# design.net
KiCad netlist of a schematic drawn in Altium Designer
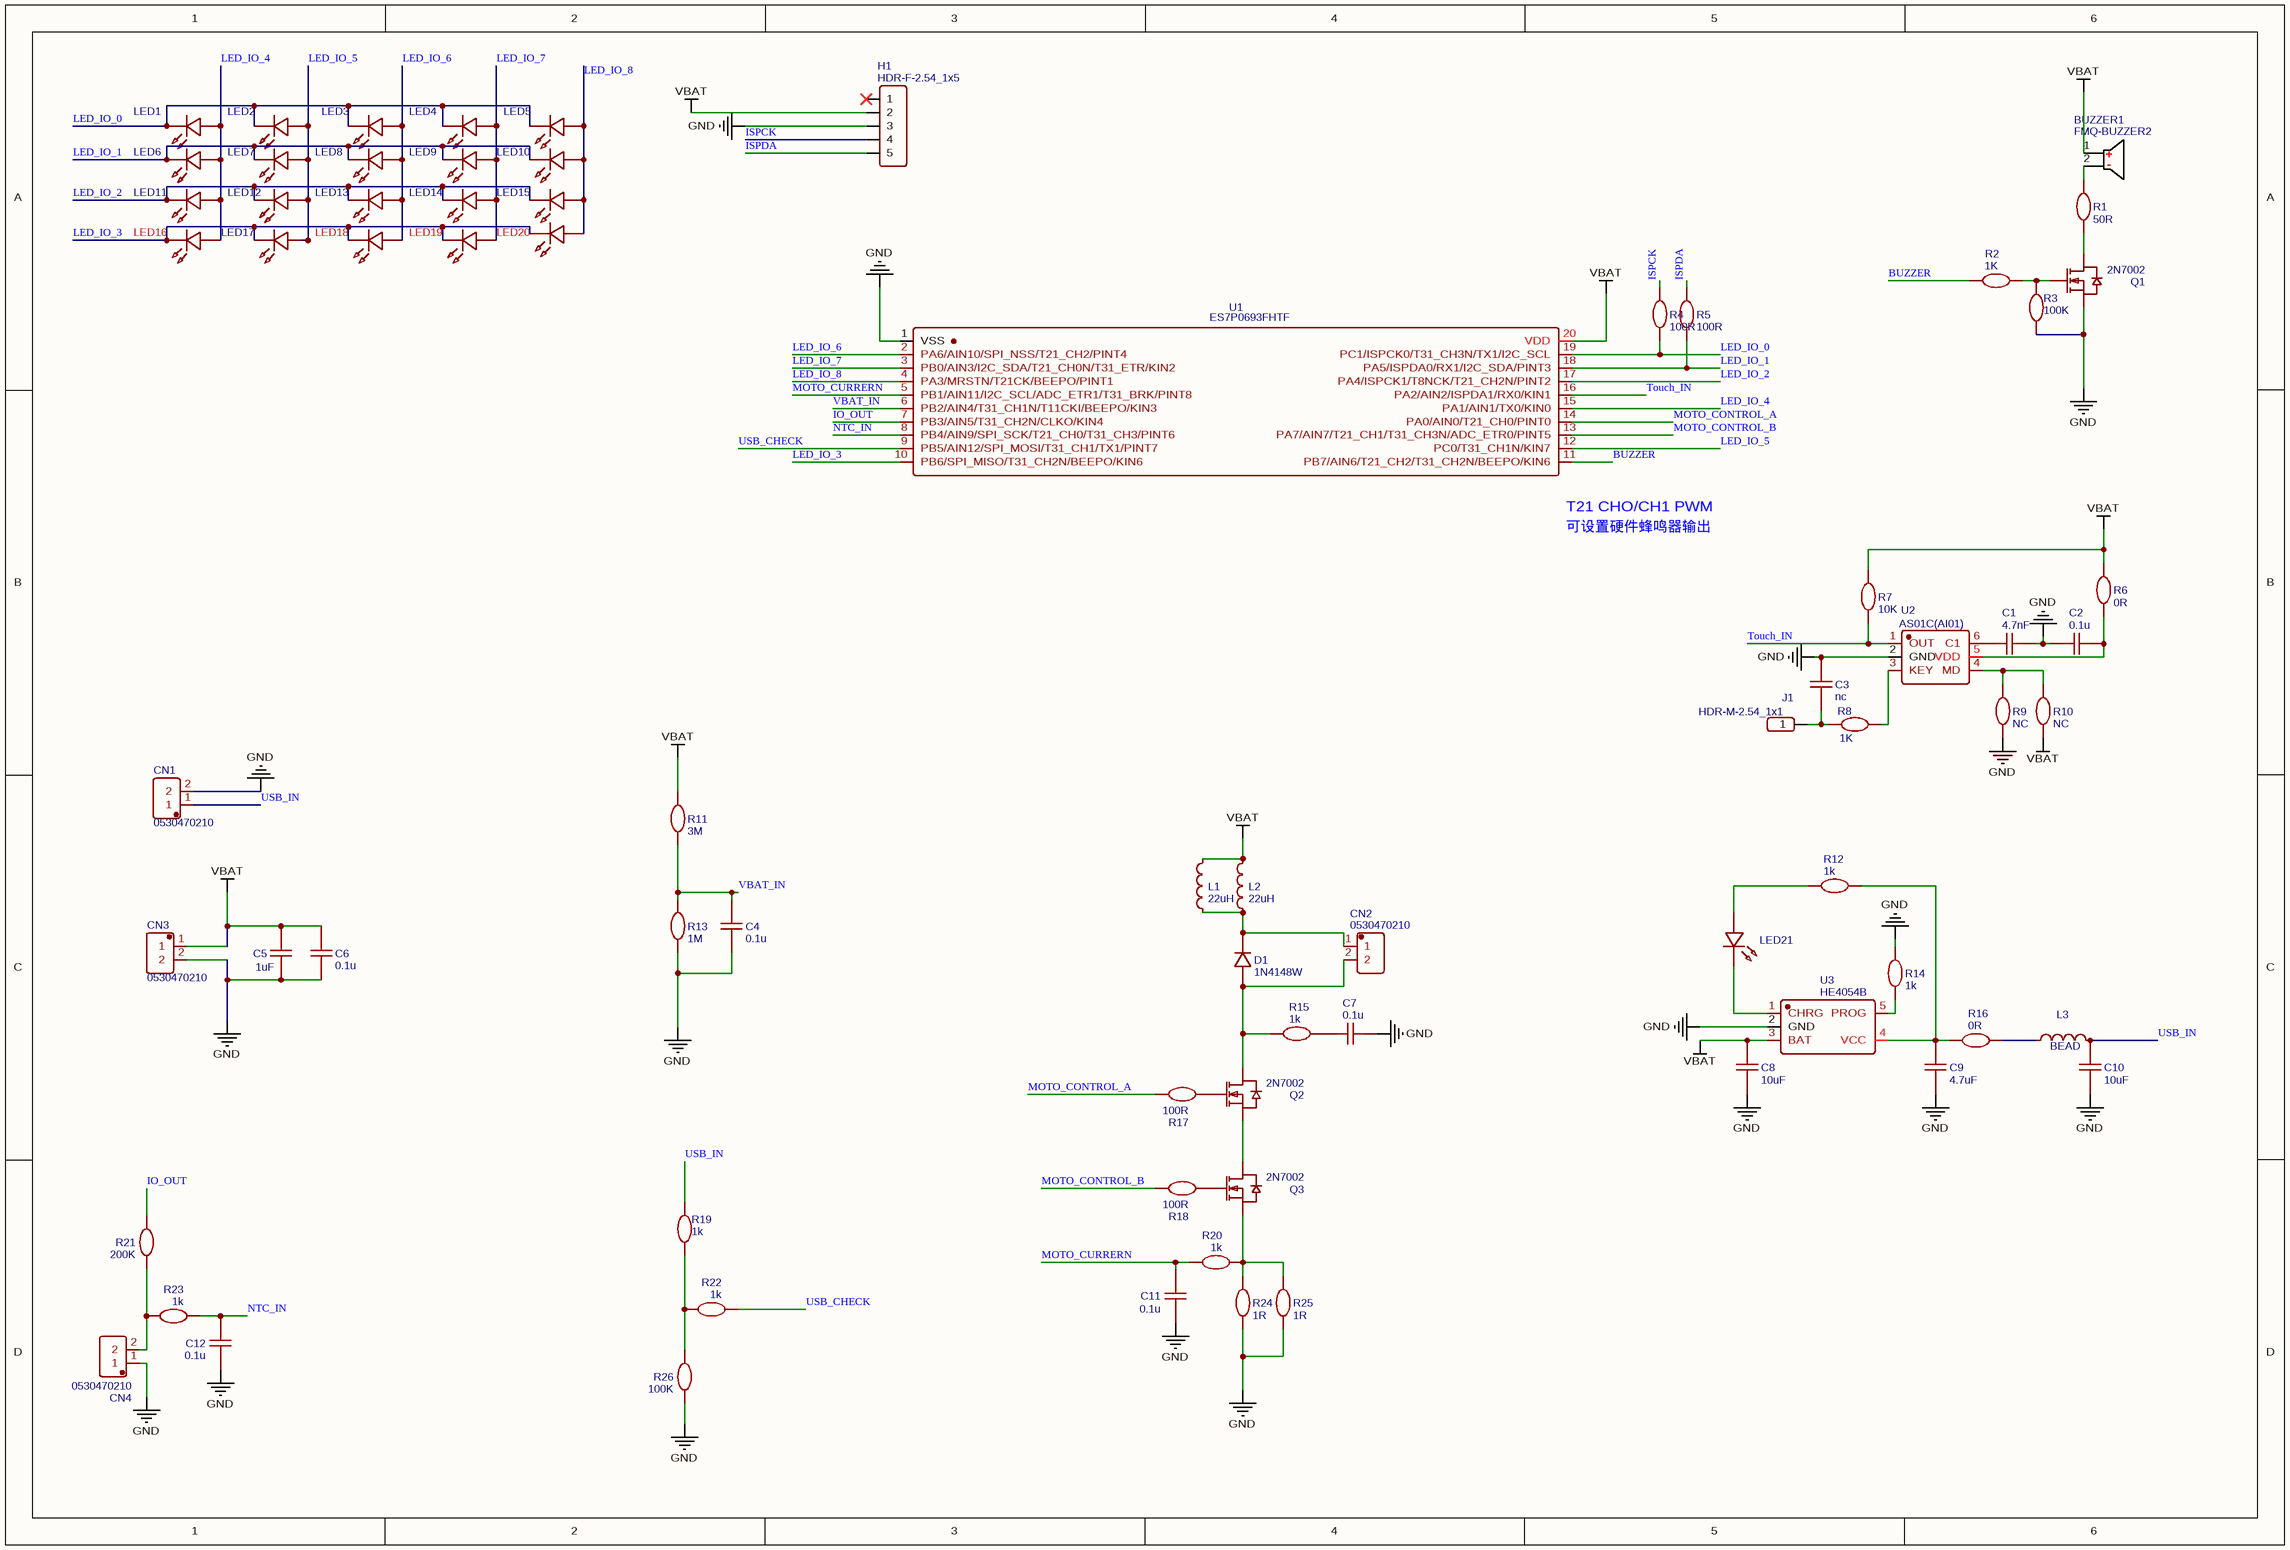
[diagram p0: 搅拌杯原理图.schdoc]

(export (version "E")
  (design (tool "Eeschema 10.0.6"))
  (components
    (comp (ref "BUZZER1")
      (value "FMQ-BUZZER2")
      (footprint "BUZ-TH_BD12.0-P7.60-D0.6-FD")
      (fields (field (name "BOM_SUPPLIER PART") "C9900006103") (field (name "CONTRIBUTOR") "LCSC"))
      (libsource (lib "altium-import") (part "root_0_FMQ-BUZZER2_"))
    )
    (comp (ref "C1")
      (value "4.7nF")
      (footprint "C0603")
      (fields (field (name "CONTRIBUTOR") "LCEDA_Lib"))
      (libsource (lib "altium-import") (part "root_0_4.7nF_"))
    )
    (comp (ref "C2")
      (value "0.1u")
      (footprint "C0603")
      (fields (field (name "CONTRIBUTOR") "LCEDA_Lib"))
      (libsource (lib "altium-import") (part "root_0_0.1u_"))
    )
    (comp (ref "C3")
      (value "nc")
      (footprint "C0603")
      (fields (field (name "CONTRIBUTOR") "LCEDA_Lib"))
      (libsource (lib "altium-import") (part "root_1_nc_"))
    )
    (comp (ref "C4")
      (value "0.1u")
      (footprint "C0603")
      (fields (field (name "CONTRIBUTOR") "LCEDA_Lib"))
      (libsource (lib "") (part "root_1_0.1u__1"))
    )
    (comp (ref "C5")
      (value "1uF")
      (footprint "C0603")
      (fields (field (name "CONTRIBUTOR") "LCEDA_Lib"))
      (libsource (lib "altium-import") (part "root_3_1uF_"))
    )
    (comp (ref "C6")
      (value "0.1u")
      (footprint "C0603")
      (fields (field (name "CONTRIBUTOR") "LCEDA_Lib"))
      (libsource (lib "") (part "root_3_0.1u__1"))
    )
    (comp (ref "C7")
      (value "0.1u")
      (footprint "C0603")
      (fields (field (name "CONTRIBUTOR") "LCEDA_Lib"))
      (libsource (lib "altium-import") (part "root_2_0.1u_"))
    )
    (comp (ref "C8")
      (value "10uF")
      (footprint "C0603")
      (fields (field (name "CONTRIBUTOR") "LCEDA_Lib"))
      (libsource (lib "altium-import") (part "root_1_10uF_"))
    )
    (comp (ref "C9")
      (value "4.7uF")
      (footprint "C0603")
      (fields (field (name "CONTRIBUTOR") "LCEDA_Lib"))
      (libsource (lib "altium-import") (part "root_1_4.7uF_"))
    )
    (comp (ref "C10")
      (value "10uF")
      (footprint "C0603")
      (fields (field (name "CONTRIBUTOR") "LCEDA_Lib"))
      (libsource (lib "altium-import") (part "root_1_10uF_"))
    )
    (comp (ref "C11")
      (value "0.1u")
      (footprint "C0603")
      (fields (field (name "CONTRIBUTOR") "LCEDA_Lib"))
      (libsource (lib "altium-import") (part "root_1_0.1u_"))
    )
    (comp (ref "C12")
      (value "0.1u")
      (footprint "C0603")
      (fields (field (name "CONTRIBUTOR") "LCEDA_Lib"))
      (libsource (lib "altium-import") (part "root_3_0.1u_"))
    )
    (comp (ref "CN1")
      (value "0530470210")
      (footprint "CONN-TH_0530470210")
      (fields (field (name "BOM_SUPPLIER PART") "C114130") (field (name "CONTRIBUTOR") "LCSC"))
      (libsource (lib "") (part "root_0_mirrored_0530470210__1"))
    )
    (comp (ref "CN2")
      (value "0530470210")
      (footprint "CONN-TH_0530470210")
      (fields (field (name "BOM_SUPPLIER PART") "C114130") (field (name "CONTRIBUTOR") "LCSC"))
      (libsource (lib "altium-import") (part "root_0_0530470210_"))
    )
    (comp (ref "CN3")
      (value "0530470210")
      (footprint "CONN-TH_0530470210")
      (fields (field (name "BOM_SUPPLIER PART") "C114130") (field (name "CONTRIBUTOR") "LCSC"))
      (libsource (lib "altium-import") (part "root_0_mirrored_0530470210_"))
    )
    (comp (ref "CN4")
      (value "0530470210")
      (footprint "CONN-TH_0530470210")
      (fields (field (name "BOM_SUPPLIER PART") "C114130") (field (name "CONTRIBUTOR") "LCSC"))
      (libsource (lib "") (part "root_0_0530470210__1"))
    )
    (comp (ref "D1")
      (value "1N4148W")
      (footprint "SOD-123FL_L2.6-W1.6-LS3.4-RD")
      (fields (field (name "BOM_SUPPLIER PART") "C129216") (field (name "CONTRIBUTOR") "LCEDA_Lib"))
      (libsource (lib "altium-import") (part "root_1_1N4148W_"))
    )
    (comp (ref "H1")
      (value "HDR-F-2.54_1x5")
      (footprint "1.27mm_5PIN")
      (fields (field (name "BOM_SUPPLIER PART") "C50950") (field (name "CONTRIBUTOR") "LCEDA_Lib"))
      (libsource (lib "altium-import") (part "root_0_HDR-F-2.54_1x5_"))
    )
    (comp (ref "J1")
      (value "HDR-M-2.54_1x1")
      (footprint "HDR-M-2.54_1X1")
      (fields (field (name "BOM_SUPPLIER PART") "C81276") (field (name "CONTRIBUTOR") "LCEDA_Lib"))
      (libsource (lib "altium-import") (part "root_2_HDR-M-2.54_1x1_"))
    )
    (comp (ref "L1")
      (value "22uH")
      (footprint "L0603")
      (fields (field (name "CONTRIBUTOR") "LCEDA_Lib"))
      (libsource (lib "altium-import") (part "root_1_22uH_"))
    )
    (comp (ref "L2")
      (value "22uH")
      (footprint "L0603")
      (fields (field (name "CONTRIBUTOR") "LCEDA_Lib"))
      (libsource (lib "altium-import") (part "root_1_22uH_"))
    )
    (comp (ref "L3")
      (value "BEAD")
      (footprint "L0603")
      (fields (field (name "CONTRIBUTOR") "LCEDA_Lib"))
      (libsource (lib "altium-import") (part "root_0_22uH_"))
    )
    (comp (ref "LED1")
      (value "LED-0603_W")
      (footprint "LED0603-FD_WHITE")
      (fields
        (field (name "BOM_MANUFACTURER PART") "17-21SURC/S530-A3/TR8")
        (field (name "BOM_SUPPLIER PART") "C72037")
        (field (name "CONTRIBUTOR") "LCEDA_Lib")
      )
      (libsource (lib "altium-import") (part "root_2_LED-0603_W_"))
    )
    (comp (ref "LED2")
      (value "LED-0603_W")
      (footprint "LED0603-FD_WHITE")
      (fields
        (field (name "BOM_MANUFACTURER PART") "17-21SURC/S530-A3/TR8")
        (field (name "BOM_SUPPLIER PART") "C72037")
        (field (name "CONTRIBUTOR") "LCEDA_Lib")
      )
      (libsource (lib "altium-import") (part "root_2_LED-0603_W_"))
    )
    (comp (ref "LED3")
      (value "LED-0603_W")
      (footprint "LED0603-FD_WHITE")
      (fields
        (field (name "BOM_MANUFACTURER PART") "17-21SURC/S530-A3/TR8")
        (field (name "BOM_SUPPLIER PART") "C72037")
        (field (name "CONTRIBUTOR") "LCEDA_Lib")
      )
      (libsource (lib "altium-import") (part "root_2_LED-0603_W_"))
    )
    (comp (ref "LED4")
      (value "LED-0603_W")
      (footprint "LED0603-FD_WHITE")
      (fields
        (field (name "BOM_MANUFACTURER PART") "17-21SURC/S530-A3/TR8")
        (field (name "BOM_SUPPLIER PART") "C72037")
        (field (name "CONTRIBUTOR") "LCEDA_Lib")
      )
      (libsource (lib "altium-import") (part "root_2_LED-0603_W_"))
    )
    (comp (ref "LED5")
      (value "LED-0603_W")
      (footprint "LED0603-FD_WHITE")
      (fields
        (field (name "BOM_MANUFACTURER PART") "17-21SURC/S530-A3/TR8")
        (field (name "BOM_SUPPLIER PART") "C72037")
        (field (name "CONTRIBUTOR") "LCEDA_Lib")
      )
      (libsource (lib "altium-import") (part "root_2_LED-0603_W_"))
    )
    (comp (ref "LED6")
      (value "LED-0603_W")
      (footprint "LED0603-FD_WHITE")
      (fields
        (field (name "BOM_MANUFACTURER PART") "17-21SURC/S530-A3/TR8")
        (field (name "BOM_SUPPLIER PART") "C72037")
        (field (name "CONTRIBUTOR") "LCEDA_Lib")
      )
      (libsource (lib "altium-import") (part "root_2_LED-0603_W_"))
    )
    (comp (ref "LED7")
      (value "LED-0603_W")
      (footprint "LED0603-FD_WHITE")
      (fields
        (field (name "BOM_MANUFACTURER PART") "17-21SURC/S530-A3/TR8")
        (field (name "BOM_SUPPLIER PART") "C72037")
        (field (name "CONTRIBUTOR") "LCEDA_Lib")
      )
      (libsource (lib "altium-import") (part "root_2_LED-0603_W_"))
    )
    (comp (ref "LED8")
      (value "LED-0603_W")
      (footprint "LED0603-FD_WHITE")
      (fields
        (field (name "BOM_MANUFACTURER PART") "17-21SURC/S530-A3/TR8")
        (field (name "BOM_SUPPLIER PART") "C72037")
        (field (name "CONTRIBUTOR") "LCEDA_Lib")
      )
      (libsource (lib "altium-import") (part "root_2_LED-0603_W_"))
    )
    (comp (ref "LED9")
      (value "LED-0603_W")
      (footprint "LED0603-FD_WHITE")
      (fields
        (field (name "BOM_MANUFACTURER PART") "17-21SURC/S530-A3/TR8")
        (field (name "BOM_SUPPLIER PART") "C72037")
        (field (name "CONTRIBUTOR") "LCEDA_Lib")
      )
      (libsource (lib "altium-import") (part "root_2_LED-0603_W_"))
    )
    (comp (ref "LED10")
      (value "LED-0603_W")
      (footprint "LED0603-FD_WHITE")
      (fields
        (field (name "BOM_MANUFACTURER PART") "17-21SURC/S530-A3/TR8")
        (field (name "BOM_SUPPLIER PART") "C72037")
        (field (name "CONTRIBUTOR") "LCEDA_Lib")
      )
      (libsource (lib "altium-import") (part "root_2_LED-0603_W_"))
    )
    (comp (ref "LED11")
      (value "LED-0603_W")
      (footprint "LED0603-FD_WHITE")
      (fields
        (field (name "BOM_MANUFACTURER PART") "17-21SURC/S530-A3/TR8")
        (field (name "BOM_SUPPLIER PART") "C72037")
        (field (name "CONTRIBUTOR") "LCEDA_Lib")
      )
      (libsource (lib "altium-import") (part "root_2_LED-0603_W_"))
    )
    (comp (ref "LED12")
      (value "LED-0603_W")
      (footprint "LED0603-FD_WHITE")
      (fields
        (field (name "BOM_MANUFACTURER PART") "17-21SURC/S530-A3/TR8")
        (field (name "BOM_SUPPLIER PART") "C72037")
        (field (name "CONTRIBUTOR") "LCEDA_Lib")
      )
      (libsource (lib "altium-import") (part "root_2_LED-0603_W_"))
    )
    (comp (ref "LED13")
      (value "LED-0603_W")
      (footprint "LED0603-FD_WHITE")
      (fields
        (field (name "BOM_MANUFACTURER PART") "17-21SURC/S530-A3/TR8")
        (field (name "BOM_SUPPLIER PART") "C72037")
        (field (name "CONTRIBUTOR") "LCEDA_Lib")
      )
      (libsource (lib "altium-import") (part "root_2_LED-0603_W_"))
    )
    (comp (ref "LED14")
      (value "LED-0603_W")
      (footprint "LED0603-FD_WHITE")
      (fields
        (field (name "BOM_MANUFACTURER PART") "17-21SURC/S530-A3/TR8")
        (field (name "BOM_SUPPLIER PART") "C72037")
        (field (name "CONTRIBUTOR") "LCEDA_Lib")
      )
      (libsource (lib "altium-import") (part "root_2_LED-0603_W_"))
    )
    (comp (ref "LED15")
      (value "LED-0603_W")
      (footprint "LED0603-FD_WHITE")
      (fields
        (field (name "BOM_MANUFACTURER PART") "17-21SURC/S530-A3/TR8")
        (field (name "BOM_SUPPLIER PART") "C72037")
        (field (name "CONTRIBUTOR") "LCEDA_Lib")
      )
      (libsource (lib "altium-import") (part "root_2_LED-0603_W_"))
    )
    (comp (ref "LED16")
      (value "LED-0603_W")
      (footprint "LED0603-FD_WHITE")
      (fields
        (field (name "BOM_MANUFACTURER PART") "17-21SURC/S530-A3/TR8")
        (field (name "BOM_SUPPLIER PART") "C72037")
        (field (name "CONTRIBUTOR") "LCEDA_Lib")
      )
      (libsource (lib "altium-import") (part "root_2_LED-0603_W_"))
    )
    (comp (ref "LED17")
      (value "LED-0603_W")
      (footprint "LED0603-FD_WHITE")
      (fields
        (field (name "BOM_MANUFACTURER PART") "17-21SURC/S530-A3/TR8")
        (field (name "BOM_SUPPLIER PART") "C72037")
        (field (name "CONTRIBUTOR") "LCEDA_Lib")
      )
      (libsource (lib "altium-import") (part "root_2_LED-0603_W_"))
    )
    (comp (ref "LED18")
      (value "LED-0603_W")
      (footprint "LED0603-FD_WHITE")
      (fields
        (field (name "BOM_MANUFACTURER PART") "17-21SURC/S530-A3/TR8")
        (field (name "BOM_SUPPLIER PART") "C72037")
        (field (name "CONTRIBUTOR") "LCEDA_Lib")
      )
      (libsource (lib "altium-import") (part "root_2_LED-0603_W_"))
    )
    (comp (ref "LED19")
      (value "LED-0603_W")
      (footprint "LED0603-FD_WHITE")
      (fields
        (field (name "BOM_MANUFACTURER PART") "17-21SURC/S530-A3/TR8")
        (field (name "BOM_SUPPLIER PART") "C72037")
        (field (name "CONTRIBUTOR") "LCEDA_Lib")
      )
      (libsource (lib "altium-import") (part "root_2_LED-0603_W_"))
    )
    (comp (ref "LED20")
      (value "LED-0603_W")
      (footprint "LED0603-FD_WHITE")
      (fields
        (field (name "BOM_MANUFACTURER PART") "17-21SURC/S530-A3/TR8")
        (field (name "BOM_SUPPLIER PART") "C72037")
        (field (name "CONTRIBUTOR") "LCEDA_Lib")
      )
      (libsource (lib "altium-import") (part "root_2_LED-0603_W_"))
    )
    (comp (ref "LED21")
      (value "LED-0603_W")
      (footprint "LED0603-FD_WHITE")
      (fields
        (field (name "BOM_MANUFACTURER PART") "17-21SURC/S530-A3/TR8")
        (field (name "BOM_SUPPLIER PART") "C72037")
        (field (name "CONTRIBUTOR") "LCEDA_Lib")
      )
      (libsource (lib "altium-import") (part "root_3_LED-0603_W_"))
    )
    (comp (ref "Q1")
      (value "2N7002")
      (footprint "SOT-23_L2.9-W1.3-P0.95-LS2.4-BR")
      (fields
        (field (name "BOM_MANUFACTURER PART") "2N7002,215")
        (field (name "BOM_SUPPLIER PART") "C65189")
        (field (name "CONTRIBUTOR") "LCEDA_Lib")
      )
      (libsource (lib "altium-import") (part "root_2_2N7002_"))
    )
    (comp (ref "Q2")
      (value "2N7002")
      (footprint "SOT-23_L2.9-W1.3-P0.95-LS2.4-BR")
      (fields
        (field (name "BOM_MANUFACTURER PART") "2N7002,215")
        (field (name "BOM_SUPPLIER PART") "C65189")
        (field (name "CONTRIBUTOR") "LCEDA_Lib")
      )
      (libsource (lib "altium-import") (part "root_2_2N7002_"))
    )
    (comp (ref "Q3")
      (value "2N7002")
      (footprint "SOT-23_L2.9-W1.3-P0.95-LS2.4-BR")
      (fields
        (field (name "BOM_MANUFACTURER PART") "2N7002,215")
        (field (name "BOM_SUPPLIER PART") "C65189")
        (field (name "CONTRIBUTOR") "LCEDA_Lib")
      )
      (libsource (lib "altium-import") (part "root_2_2N7002_"))
    )
    (comp (ref "R1")
      (value "50R")
      (footprint "R0603")
      (fields (field (name "CONTRIBUTOR") "LCEDA_Lib"))
      (libsource (lib "altium-import") (part "root_3_100R_"))
    )
    (comp (ref "R2")
      (value "1K")
      (footprint "R0603")
      (fields (field (name "CONTRIBUTOR") "LCEDA_Lib"))
      (libsource (lib "altium-import") (part "root_2_1K_"))
    )
    (comp (ref "R3")
      (value "100K")
      (footprint "R0603")
      (fields (field (name "CONTRIBUTOR") "LCEDA_Lib"))
      (libsource (lib "altium-import") (part "root_3_1K_"))
    )
    (comp (ref "R4")
      (value "100R")
      (footprint "R0603")
      (fields (field (name "CONTRIBUTOR") "LCEDA_Lib"))
      (libsource (lib "altium-import") (part "root_3_100R_"))
    )
    (comp (ref "R5")
      (value "100R")
      (footprint "R0603")
      (fields (field (name "CONTRIBUTOR") "LCEDA_Lib"))
      (libsource (lib "altium-import") (part "root_3_100R_"))
    )
    (comp (ref "R6")
      (value "0R")
      (footprint "R0603")
      (fields (field (name "CONTRIBUTOR") "LCEDA_Lib"))
      (libsource (lib "altium-import") (part "root_1_NC_"))
    )
    (comp (ref "R7")
      (value "10K")
      (footprint "R0603")
      (fields (field (name "CONTRIBUTOR") "LCEDA_Lib"))
      (libsource (lib "altium-import") (part "root_1_NC_"))
    )
    (comp (ref "R8")
      (value "1K")
      (footprint "R0603")
      (fields (field (name "CONTRIBUTOR") "LCEDA_Lib"))
      (libsource (lib "altium-import") (part "root_2_1K_"))
    )
    (comp (ref "R9")
      (value "NC")
      (footprint "R0603")
      (fields (field (name "CONTRIBUTOR") "LCEDA_Lib"))
      (libsource (lib "altium-import") (part "root_1_NC_"))
    )
    (comp (ref "R10")
      (value "NC")
      (footprint "R0603")
      (fields (field (name "CONTRIBUTOR") "LCEDA_Lib"))
      (libsource (lib "altium-import") (part "root_1_NC_"))
    )
    (comp (ref "R11")
      (value "3M")
      (footprint "R0603")
      (fields (field (name "CONTRIBUTOR") "LCEDA_Lib"))
      (libsource (lib "altium-import") (part "root_1_430k_"))
    )
    (comp (ref "R12")
      (value "1k")
      (footprint "R0603")
      (fields (field (name "CONTRIBUTOR") "LCEDA_Lib"))
      (libsource (lib "") (part "root_2_1k__1"))
    )
    (comp (ref "R13")
      (value "1M")
      (footprint "R0603")
      (fields (field (name "CONTRIBUTOR") "LCEDA_Lib"))
      (libsource (lib "altium-import") (part "root_1_430K_"))
    )
    (comp (ref "R14")
      (value "1k")
      (footprint "R0603")
      (fields (field (name "CONTRIBUTOR") "LCEDA_Lib"))
      (libsource (lib "altium-import") (part "root_1_1k_"))
    )
    (comp (ref "R15")
      (value "1k")
      (footprint "R0603")
      (fields (field (name "CONTRIBUTOR") "LCEDA_Lib"))
      (libsource (lib "") (part "root_2_1k__1"))
    )
    (comp (ref "R16")
      (value "0R")
      (footprint "R0603")
      (fields (field (name "CONTRIBUTOR") "LCEDA_Lib"))
      (libsource (lib "altium-import") (part "root_0_NC_"))
    )
    (comp (ref "R17")
      (value "100R")
      (footprint "R0603")
      (fields (field (name "CONTRIBUTOR") "LCEDA_Lib"))
      (libsource (lib "altium-import") (part "root_2_100R_"))
    )
    (comp (ref "R18")
      (value "100R")
      (footprint "R0603")
      (fields (field (name "CONTRIBUTOR") "LCEDA_Lib"))
      (libsource (lib "altium-import") (part "root_2_100R_"))
    )
    (comp (ref "R19")
      (value "1k")
      (footprint "R0603")
      (fields (field (name "CONTRIBUTOR") "LCEDA_Lib"))
      (libsource (lib "altium-import") (part "root_3_1k_"))
    )
    (comp (ref "R20")
      (value "1k")
      (footprint "R0603")
      (fields (field (name "CONTRIBUTOR") "LCEDA_Lib"))
      (libsource (lib "altium-import") (part "root_0_1k_"))
    )
    (comp (ref "R21")
      (value "200K")
      (footprint "R0603")
      (fields (field (name "CONTRIBUTOR") "LCEDA_Lib"))
      (libsource (lib "altium-import") (part "root_3_33K_"))
    )
    (comp (ref "R22")
      (value "1k")
      (footprint "R0603")
      (fields (field (name "CONTRIBUTOR") "LCEDA_Lib"))
      (libsource (lib "altium-import") (part "root_2_1k_"))
    )
    (comp (ref "R23")
      (value "1k")
      (footprint "R0603")
      (fields (field (name "CONTRIBUTOR") "LCEDA_Lib"))
      (libsource (lib "altium-import") (part "root_2_1k_"))
    )
    (comp (ref "R24")
      (value "1R")
      (footprint "R1206")
      (fields (field (name "CONTRIBUTOR") "LCEDA_Lib"))
      (libsource (lib "altium-import") (part "root_1_1R_"))
    )
    (comp (ref "R25")
      (value "1R")
      (footprint "R1206")
      (fields (field (name "CONTRIBUTOR") "LCEDA_Lib"))
      (libsource (lib "altium-import") (part "root_1_1R_"))
    )
    (comp (ref "R26")
      (value "100K")
      (footprint "R0603")
      (fields (field (name "CONTRIBUTOR") "LCEDA_Lib"))
      (libsource (lib "altium-import") (part "root_3_33K_"))
    )
    (comp (ref "U1")
      (value "ES7P0693FHTF")
      (footprint "TSOP20")
      (fields (field (name "CONTRIBUTOR") "zime_zl"))
      (libsource (lib "altium-import") (part "root_0_ES7P0693FHTF_"))
    )
    (comp (ref "U2")
      (value "AS01C(AI01)")
      (footprint "SOT-23-6_L2.9-W1.6-P0.95-LS2.8-BL")
      (fields (field (name "BOM_SUPPLIER PART") "C389617") (field (name "CONTRIBUTOR") "LCSC"))
      (libsource (lib "altium-import") (part "root_0_AS01C(AI01)_"))
    )
    (comp (ref "U3")
      (value "HE4054B")
      (footprint "SOT-23-5_L3.0-W1.7-P0.95-LS2.8-BR")
      (fields (field (name "BOM_SUPPLIER PART") "C711953") (field (name "CONTRIBUTOR") "LCSC"))
      (libsource (lib "altium-import") (part "root_0_HE4054B_"))
    )
  )
  (nets
    (net (code "1") (name "/BUZZER") (class "Default")
      (node (ref "R2") (pin "2") (pinfunction "2_2") (pintype "passive"))
      (node (ref "U1") (pin "11") (pinfunction "PB7/AIN6/T21_CH2/T31_CH2N/BEEPO/KIN6_11") (pintype "passive"))
    )
    (net (code "2") (name "/IO_OUT") (class "Default")
      (node (ref "R21") (pin "1") (pinfunction "1_1") (pintype "passive"))
      (node (ref "U1") (pin "7") (pinfunction "PB3/AIN5/T31_CH2N/CLKO/KIN4_7") (pintype "passive"))
    )
    (net (code "3") (name "/ISPCK") (class "Default")
      (node (ref "H1") (pin "4") (pinfunction "4_4") (pintype "passive"))
      (node (ref "R4") (pin "1") (pinfunction "1_1") (pintype "passive"))
    )
    (net (code "4") (name "/ISPDA") (class "Default")
      (node (ref "H1") (pin "5") (pinfunction "5_5") (pintype "passive"))
      (node (ref "R5") (pin "1") (pinfunction "1_1") (pintype "passive"))
    )
    (net (code "5") (name "/LED_IO_0") (class "Default")
      (node (ref "LED1") (pin "2") (pinfunction "2_2") (pintype "passive"))
      (node (ref "LED2") (pin "2") (pinfunction "2_2") (pintype "passive"))
      (node (ref "LED3") (pin "2") (pinfunction "2_2") (pintype "passive"))
      (node (ref "LED4") (pin "2") (pinfunction "2_2") (pintype "passive"))
      (node (ref "LED5") (pin "2") (pinfunction "2_2") (pintype "passive"))
      (node (ref "R4") (pin "2") (pinfunction "2_2") (pintype "passive"))
      (node (ref "U1") (pin "19") (pinfunction "PC1/ISPCK0/T31_CH3N/TX1/I2C_SCL_19") (pintype "passive"))
    )
    (net (code "6") (name "/LED_IO_1") (class "Default")
      (node (ref "LED10") (pin "2") (pinfunction "2_2") (pintype "passive"))
      (node (ref "LED6") (pin "2") (pinfunction "2_2") (pintype "passive"))
      (node (ref "LED7") (pin "2") (pinfunction "2_2") (pintype "passive"))
      (node (ref "LED8") (pin "2") (pinfunction "2_2") (pintype "passive"))
      (node (ref "LED9") (pin "2") (pinfunction "2_2") (pintype "passive"))
      (node (ref "R5") (pin "2") (pinfunction "2_2") (pintype "passive"))
      (node (ref "U1") (pin "18") (pinfunction "PA5/ISPDA0/RX1/I2C_SDA/PINT3_18") (pintype "passive"))
    )
    (net (code "7") (name "/LED_IO_2") (class "Default")
      (node (ref "LED11") (pin "2") (pinfunction "2_2") (pintype "passive"))
      (node (ref "LED12") (pin "2") (pinfunction "2_2") (pintype "passive"))
      (node (ref "LED13") (pin "2") (pinfunction "2_2") (pintype "passive"))
      (node (ref "LED14") (pin "2") (pinfunction "2_2") (pintype "passive"))
      (node (ref "LED15") (pin "2") (pinfunction "2_2") (pintype "passive"))
      (node (ref "U1") (pin "17") (pinfunction "PA4/ISPCK1/T8NCK/T21_CH2N/PINT2_17") (pintype "passive"))
    )
    (net (code "8") (name "/LED_IO_3") (class "Default")
      (node (ref "LED16") (pin "2") (pinfunction "2_2") (pintype "passive"))
      (node (ref "LED17") (pin "2") (pinfunction "2_2") (pintype "passive"))
      (node (ref "LED18") (pin "2") (pinfunction "2_2") (pintype "passive"))
      (node (ref "LED19") (pin "2") (pinfunction "2_2") (pintype "passive"))
      (node (ref "LED20") (pin "2") (pinfunction "2_2") (pintype "passive"))
      (node (ref "U1") (pin "10") (pinfunction "PB6/SPI_MISO/T31_CH2N/BEEPO/KIN6_10") (pintype "passive"))
    )
    (net (code "9") (name "/LED_IO_4") (class "Default")
      (node (ref "LED1") (pin "1") (pinfunction "1_1") (pintype "passive"))
      (node (ref "LED11") (pin "1") (pinfunction "1_1") (pintype "passive"))
      (node (ref "LED16") (pin "1") (pinfunction "1_1") (pintype "passive"))
      (node (ref "LED6") (pin "1") (pinfunction "1_1") (pintype "passive"))
      (node (ref "U1") (pin "15") (pinfunction "PA1/AIN1/TX0/KIN0_15") (pintype "passive"))
    )
    (net (code "10") (name "/LED_IO_5") (class "Default")
      (node (ref "LED12") (pin "1") (pinfunction "1_1") (pintype "passive"))
      (node (ref "LED17") (pin "1") (pinfunction "1_1") (pintype "passive"))
      (node (ref "LED2") (pin "1") (pinfunction "1_1") (pintype "passive"))
      (node (ref "LED7") (pin "1") (pinfunction "1_1") (pintype "passive"))
      (node (ref "U1") (pin "12") (pinfunction "PC0/T31_CH1N/KIN7_12") (pintype "passive"))
    )
    (net (code "11") (name "/LED_IO_6") (class "Default")
      (node (ref "LED13") (pin "1") (pinfunction "1_1") (pintype "passive"))
      (node (ref "LED18") (pin "1") (pinfunction "1_1") (pintype "passive"))
      (node (ref "LED3") (pin "1") (pinfunction "1_1") (pintype "passive"))
      (node (ref "LED8") (pin "1") (pinfunction "1_1") (pintype "passive"))
      (node (ref "U1") (pin "2") (pinfunction "PA6/AIN10/SPI_NSS/T21_CH2/PINT4_2") (pintype "passive"))
    )
    (net (code "12") (name "/LED_IO_7") (class "Default")
      (node (ref "LED14") (pin "1") (pinfunction "1_1") (pintype "passive"))
      (node (ref "LED19") (pin "1") (pinfunction "1_1") (pintype "passive"))
      (node (ref "LED4") (pin "1") (pinfunction "1_1") (pintype "passive"))
      (node (ref "LED9") (pin "1") (pinfunction "1_1") (pintype "passive"))
      (node (ref "U1") (pin "3") (pinfunction "PB0/AIN3/I2C_SDA/T21_CH0N/T31_ETR/KIN2_3") (pintype "passive"))
    )
    (net (code "13") (name "/LED_IO_8") (class "Default")
      (node (ref "LED10") (pin "1") (pinfunction "1_1") (pintype "passive"))
      (node (ref "LED15") (pin "1") (pinfunction "1_1") (pintype "passive"))
      (node (ref "LED20") (pin "1") (pinfunction "1_1") (pintype "passive"))
      (node (ref "LED5") (pin "1") (pinfunction "1_1") (pintype "passive"))
      (node (ref "U1") (pin "4") (pinfunction "PA3/MRSTN/T21CK/BEEPO/PINT1_4") (pintype "passive"))
    )
    (net (code "14") (name "/MOTO_CONTROL_A") (class "Default")
      (node (ref "R17") (pin "1") (pinfunction "1_1") (pintype "passive"))
      (node (ref "U1") (pin "14") (pinfunction "PA0/AIN0/T21_CH0/PINT0_14") (pintype "passive"))
    )
    (net (code "15") (name "/MOTO_CONTROL_B") (class "Default")
      (node (ref "R18") (pin "1") (pinfunction "1_1") (pintype "passive"))
      (node (ref "U1") (pin "13") (pinfunction "PA7/AIN7/T21_CH1/T31_CH3N/ADC_ETR0/PINT5_13") (pintype "passive"))
    )
    (net (code "16") (name "/MOTO_CURRERN") (class "Default")
      (node (ref "C11") (pin "2") (pinfunction "2_2") (pintype "passive"))
      (node (ref "R20") (pin "2") (pinfunction "2_2") (pintype "passive"))
      (node (ref "U1") (pin "5") (pinfunction "PB1/AIN11/I2C_SCL/ADC_ETR1/T31_BRK/PINT8_5") (pintype "passive"))
    )
    (net (code "17") (name "/NTC_IN") (class "Default")
      (node (ref "C12") (pin "1") (pinfunction "1_1") (pintype "passive"))
      (node (ref "R23") (pin "2") (pinfunction "2_2") (pintype "passive"))
      (node (ref "U1") (pin "8") (pinfunction "PB4/AIN9/SPI_SCK/T21_CH0/T31_CH3/PINT6_8") (pintype "passive"))
    )
    (net (code "18") (name "/Touch_IN") (class "Default")
      (node (ref "R7") (pin "1") (pinfunction "1_1") (pintype "passive"))
      (node (ref "U1") (pin "16") (pinfunction "PA2/AIN2/ISPDA1/RX0/KIN1_16") (pintype "passive"))
      (node (ref "U2") (pin "1") (pinfunction "OUT_1") (pintype "passive"))
    )
    (net (code "19") (name "/USB_CHECK") (class "Default")
      (node (ref "R22") (pin "2") (pinfunction "2_2") (pintype "passive"))
      (node (ref "U1") (pin "9") (pinfunction "PB5/AIN12/SPI_MOSI/T31_CH1/TX1/PINT7_9") (pintype "passive"))
    )
    (net (code "20") (name "/USB_IN") (class "Default")
      (node (ref "C10") (pin "2") (pinfunction "2_2") (pintype "passive"))
      (node (ref "CN1") (pin "1") (pinfunction "1_1") (pintype "passive"))
      (node (ref "L3") (pin "2") (pinfunction "2_2") (pintype "passive"))
      (node (ref "R19") (pin "2") (pinfunction "2_2") (pintype "passive"))
    )
    (net (code "21") (name "/VBAT_IN") (class "Default")
      (node (ref "C4") (pin "2") (pinfunction "2_2") (pintype "passive"))
      (node (ref "R11") (pin "1") (pinfunction "1_1") (pintype "passive"))
      (node (ref "R13") (pin "2") (pinfunction "2_2") (pintype "passive"))
      (node (ref "U1") (pin "6") (pinfunction "PB2/AIN4/T31_CH1N/T11CKI/BEEPO/KIN3_6") (pintype "passive"))
    )
    (net (code "22") (name "GND") (class "Default")
      (node (ref "C1") (pin "2") (pinfunction "2_2") (pintype "passive"))
      (node (ref "C10") (pin "1") (pinfunction "1_1") (pintype "passive"))
      (node (ref "C11") (pin "1") (pinfunction "1_1") (pintype "passive"))
      (node (ref "C12") (pin "2") (pinfunction "2_2") (pintype "passive"))
      (node (ref "C2") (pin "1") (pinfunction "1_1") (pintype "passive"))
      (node (ref "C3") (pin "2") (pinfunction "2_2") (pintype "passive"))
      (node (ref "C4") (pin "1") (pinfunction "1_1") (pintype "passive"))
      (node (ref "C5") (pin "2") (pinfunction "2_2") (pintype "passive"))
      (node (ref "C6") (pin "2") (pinfunction "2_2") (pintype "passive"))
      (node (ref "C7") (pin "1") (pinfunction "1_1") (pintype "passive"))
      (node (ref "C8") (pin "1") (pinfunction "1_1") (pintype "passive"))
      (node (ref "C9") (pin "1") (pinfunction "1_1") (pintype "passive"))
      (node (ref "CN1") (pin "2") (pinfunction "2_2") (pintype "passive"))
      (node (ref "CN3") (pin "2") (pinfunction "2_2") (pintype "passive"))
      (node (ref "CN4") (pin "1") (pinfunction "1_1") (pintype "passive"))
      (node (ref "H1") (pin "3") (pinfunction "3_3") (pintype "passive"))
      (node (ref "Q1") (pin "2") (pinfunction "S_2") (pintype "passive"))
      (node (ref "R13") (pin "1") (pinfunction "1_1") (pintype "passive"))
      (node (ref "R14") (pin "2") (pinfunction "2_2") (pintype "passive"))
      (node (ref "R24") (pin "1") (pinfunction "1_1") (pintype "passive"))
      (node (ref "R25") (pin "1") (pinfunction "1_1") (pintype "passive"))
      (node (ref "R26") (pin "2") (pinfunction "2_2") (pintype "passive"))
      (node (ref "R3") (pin "2") (pinfunction "2_2") (pintype "passive"))
      (node (ref "R9") (pin "1") (pinfunction "1_1") (pintype "passive"))
      (node (ref "U1") (pin "1") (pinfunction "VSS_1") (pintype "passive"))
      (node (ref "U2") (pin "2") (pinfunction "GND_2") (pintype "passive"))
      (node (ref "U3") (pin "2") (pinfunction "GND_2") (pintype "passive"))
    )
    (net (code "23") (name "Net-(BUZZER1-Pad2)") (class "Default")
      (node (ref "BUZZER1") (pin "2") (pinfunction "2_2") (pintype "passive"))
      (node (ref "R1") (pin "1") (pinfunction "1_1") (pintype "passive"))
    )
    (net (code "24") (name "Net-(C3-Pad1)") (class "Default")
      (node (ref "C3") (pin "1") (pinfunction "1_1") (pintype "passive"))
      (node (ref "J1") (pin "1") (pinfunction "1_1") (pintype "passive"))
      (node (ref "R8") (pin "2") (pinfunction "2_2") (pintype "passive"))
    )
    (net (code "25") (name "Net-(C7-Pad2)") (class "Default")
      (node (ref "C7") (pin "2") (pinfunction "2_2") (pintype "passive"))
      (node (ref "R15") (pin "1") (pinfunction "1_1") (pintype "passive"))
    )
    (net (code "26") (name "Net-(CN2-Pad1)") (class "Default")
      (node (ref "CN2") (pin "1") (pinfunction "1_1") (pintype "passive"))
      (node (ref "D1") (pin "1") (pinfunction "1_1") (pintype "passive"))
      (node (ref "L1") (pin "1") (pinfunction "1_1") (pintype "passive"))
      (node (ref "L2") (pin "1") (pinfunction "1_1") (pintype "passive"))
    )
    (net (code "27") (name "Net-(CN4-Pad2)") (class "Default")
      (node (ref "CN4") (pin "2") (pinfunction "2_2") (pintype "passive"))
      (node (ref "R21") (pin "2") (pinfunction "2_2") (pintype "passive"))
      (node (ref "R23") (pin "1") (pinfunction "1_1") (pintype "passive"))
    )
    (net (code "28") (name "Net-(L3-Pad1)") (class "Default")
      (node (ref "L3") (pin "1") (pinfunction "1_1") (pintype "passive"))
      (node (ref "R16") (pin "2") (pinfunction "2_2") (pintype "passive"))
    )
    (net (code "29") (name "Net-(LED21-Pad1)") (class "Default")
      (node (ref "LED21") (pin "1") (pinfunction "1_1") (pintype "passive"))
      (node (ref "R12") (pin "2") (pinfunction "2_2") (pintype "passive"))
    )
    (net (code "30") (name "Net-(Q1-D)") (class "Default")
      (node (ref "Q1") (pin "3") (pinfunction "D_3") (pintype "passive"))
      (node (ref "R1") (pin "2") (pinfunction "2_2") (pintype "passive"))
    )
    (net (code "31") (name "Net-(Q1-G)") (class "Default")
      (node (ref "Q1") (pin "1") (pinfunction "G_1") (pintype "passive"))
      (node (ref "R2") (pin "1") (pinfunction "1_1") (pintype "passive"))
      (node (ref "R3") (pin "1") (pinfunction "1_1") (pintype "passive"))
    )
    (net (code "32") (name "Net-(Q2-D)") (class "Default")
      (node (ref "CN2") (pin "2") (pinfunction "2_2") (pintype "passive"))
      (node (ref "D1") (pin "2") (pinfunction "2_2") (pintype "passive"))
      (node (ref "Q2") (pin "3") (pinfunction "D_3") (pintype "passive"))
      (node (ref "R15") (pin "2") (pinfunction "2_2") (pintype "passive"))
    )
    (net (code "33") (name "Net-(Q2-G)") (class "Default")
      (node (ref "Q2") (pin "1") (pinfunction "G_1") (pintype "passive"))
      (node (ref "R17") (pin "2") (pinfunction "2_2") (pintype "passive"))
    )
    (net (code "34") (name "Net-(Q2-S)") (class "Default")
      (node (ref "Q2") (pin "2") (pinfunction "S_2") (pintype "passive"))
      (node (ref "Q3") (pin "3") (pinfunction "D_3") (pintype "passive"))
    )
    (net (code "35") (name "Net-(Q3-G)") (class "Default")
      (node (ref "Q3") (pin "1") (pinfunction "G_1") (pintype "passive"))
      (node (ref "R18") (pin "2") (pinfunction "2_2") (pintype "passive"))
    )
    (net (code "36") (name "Net-(Q3-S)") (class "Default")
      (node (ref "Q3") (pin "2") (pinfunction "S_2") (pintype "passive"))
      (node (ref "R20") (pin "1") (pinfunction "1_1") (pintype "passive"))
      (node (ref "R24") (pin "2") (pinfunction "2_2") (pintype "passive"))
      (node (ref "R25") (pin "2") (pinfunction "2_2") (pintype "passive"))
    )
    (net (code "37") (name "Net-(R19-Pad1)") (class "Default")
      (node (ref "R19") (pin "1") (pinfunction "1_1") (pintype "passive"))
      (node (ref "R22") (pin "1") (pinfunction "1_1") (pintype "passive"))
      (node (ref "R26") (pin "1") (pinfunction "1_1") (pintype "passive"))
    )
    (net (code "38") (name "Net-(U2-C1)") (class "Default")
      (node (ref "C1") (pin "1") (pinfunction "1_1") (pintype "passive"))
      (node (ref "U2") (pin "6") (pinfunction "C1_6") (pintype "passive"))
    )
    (net (code "39") (name "Net-(U2-KEY)") (class "Default")
      (node (ref "R8") (pin "1") (pinfunction "1_1") (pintype "passive"))
      (node (ref "U2") (pin "3") (pinfunction "KEY_3") (pintype "passive"))
    )
    (net (code "40") (name "Net-(U2-MD)") (class "Default")
      (node (ref "R10") (pin "2") (pinfunction "2_2") (pintype "passive"))
      (node (ref "R9") (pin "2") (pinfunction "2_2") (pintype "passive"))
      (node (ref "U2") (pin "4") (pinfunction "MD_4") (pintype "passive"))
    )
    (net (code "41") (name "Net-(U2-VDD)") (class "Default")
      (node (ref "C2") (pin "2") (pinfunction "2_2") (pintype "passive"))
      (node (ref "R6") (pin "1") (pinfunction "1_1") (pintype "passive"))
      (node (ref "U2") (pin "5") (pinfunction "VDD_5") (pintype "passive"))
    )
    (net (code "42") (name "Net-(U3-CHRG)") (class "Default")
      (node (ref "LED21") (pin "2") (pinfunction "2_2") (pintype "passive"))
      (node (ref "U3") (pin "1") (pinfunction "CHRG_1") (pintype "passive"))
    )
    (net (code "43") (name "Net-(U3-PROG)") (class "Default")
      (node (ref "R14") (pin "1") (pinfunction "1_1") (pintype "passive"))
      (node (ref "U3") (pin "5") (pinfunction "PROG_5") (pintype "passive"))
    )
    (net (code "44") (name "Net-(U3-VCC)") (class "Default")
      (node (ref "C9") (pin "2") (pinfunction "2_2") (pintype "passive"))
      (node (ref "R12") (pin "1") (pinfunction "1_1") (pintype "passive"))
      (node (ref "R16") (pin "1") (pinfunction "1_1") (pintype "passive"))
      (node (ref "U3") (pin "4") (pinfunction "VCC_4") (pintype "passive"))
    )
    (net (code "45") (name "VBAT") (class "Default")
      (node (ref "BUZZER1") (pin "1") (pinfunction "1_1") (pintype "passive"))
      (node (ref "C5") (pin "1") (pinfunction "1_1") (pintype "passive"))
      (node (ref "C6") (pin "1") (pinfunction "1_1") (pintype "passive"))
      (node (ref "C8") (pin "2") (pinfunction "2_2") (pintype "passive"))
      (node (ref "CN3") (pin "1") (pinfunction "1_1") (pintype "passive"))
      (node (ref "H1") (pin "2") (pinfunction "2_2") (pintype "passive"))
      (node (ref "L1") (pin "2") (pinfunction "2_2") (pintype "passive"))
      (node (ref "L2") (pin "2") (pinfunction "2_2") (pintype "passive"))
      (node (ref "R10") (pin "1") (pinfunction "1_1") (pintype "passive"))
      (node (ref "R11") (pin "2") (pinfunction "2_2") (pintype "passive"))
      (node (ref "R6") (pin "2") (pinfunction "2_2") (pintype "passive"))
      (node (ref "R7") (pin "2") (pinfunction "2_2") (pintype "passive"))
      (node (ref "U1") (pin "20") (pinfunction "VDD_20") (pintype "passive"))
      (node (ref "U3") (pin "3") (pinfunction "BAT_3") (pintype "passive"))
    )
    (net (code "46") (name "unconnected-(H1-Pad1)") (class "Default")
      (node (ref "H1") (pin "1") (pinfunction "1_1") (pintype "passive+no_connect"))
    )
  )
)
